# Active_crossover_V12_SMD.net
KiCad netlist of a schematic drawn in EAGLE
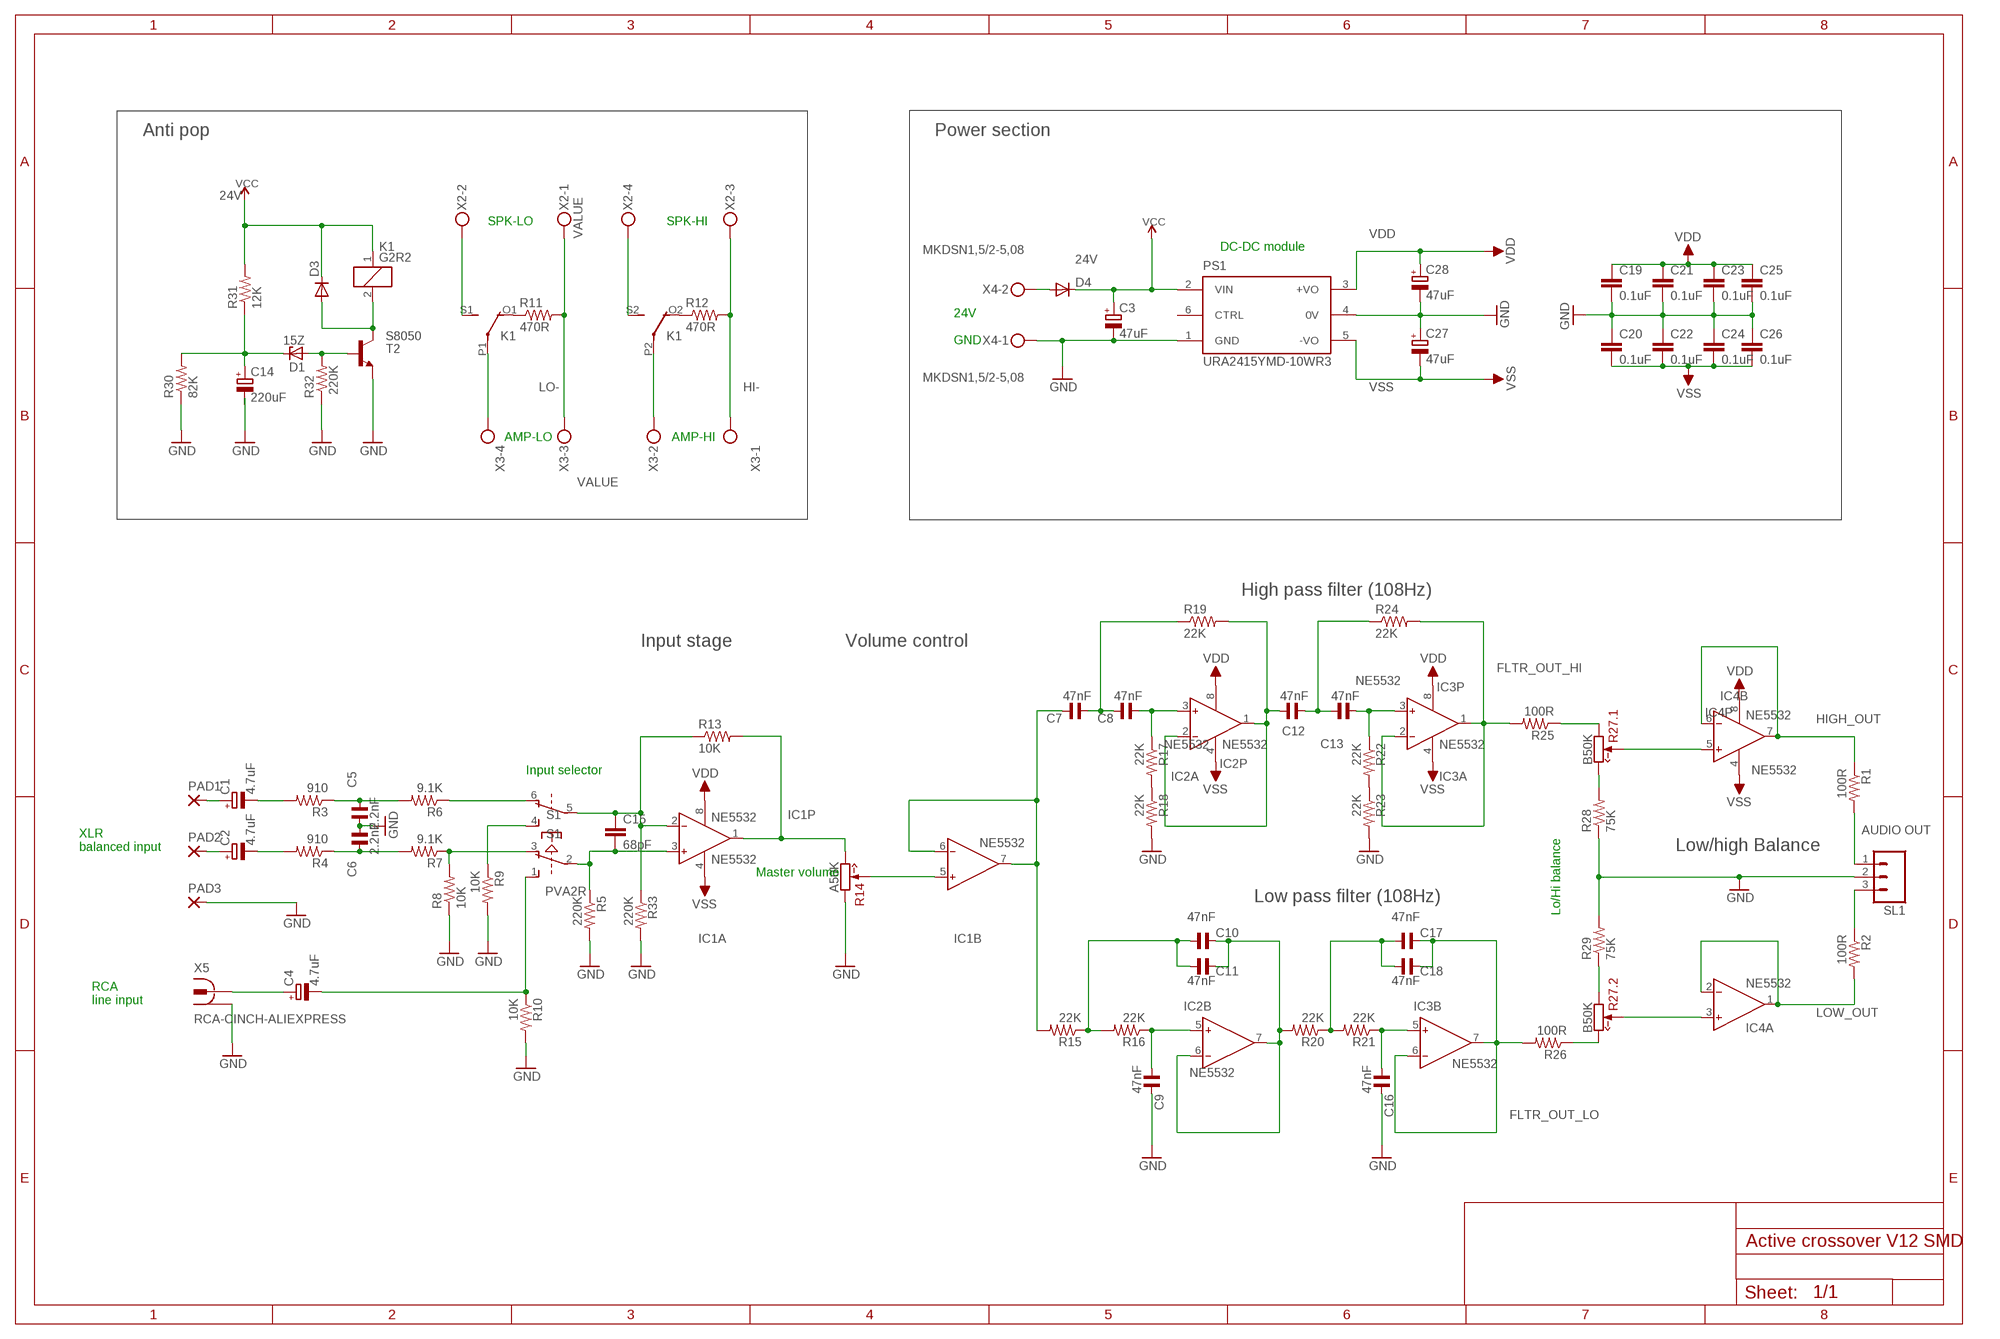
[diagram p0: schematic, sheet 1]

(export (version "E")
  (design (tool "Eeschema 10.0.6"))
  (components
    (comp (ref "C1")
      (value "4.7uF")
      (footprint "eagle-import:E2-5")
      (libsource (lib "eagle-import") (part "rcl_334_CPOL-EUE2-5"))
    )
    (comp (ref "C2")
      (value "4.7uF")
      (footprint "eagle-import:E2-5")
      (libsource (lib "eagle-import") (part "rcl_334_CPOL-EUE2-5"))
    )
    (comp (ref "C3")
      (value "47uF")
      (footprint "eagle-import:E2,5-6")
      (libsource (lib "eagle-import") (part "rcl_334_CPOL-EUE2.5-6"))
    )
    (comp (ref "C4")
      (value "4.7uF")
      (footprint "eagle-import:E2-5")
      (libsource (lib "eagle-import") (part "rcl_334_CPOL-EUE2-5"))
    )
    (comp (ref "C5")
      (value "2.2nF")
      (footprint "eagle-import:C050-025X072")
      (libsource (lib "eagle-import") (part "C_C050-025X072"))
    )
    (comp (ref "C6")
      (value "2.2nF")
      (footprint "eagle-import:C050-025X072")
      (libsource (lib "eagle-import") (part "C_C050-025X072"))
    )
    (comp (ref "C7")
      (value "47nF")
      (footprint "eagle-import:C050-025X072")
      (libsource (lib "eagle-import") (part "C_C050-025X072"))
    )
    (comp (ref "C8")
      (value "47nF")
      (footprint "eagle-import:C050-025X072")
      (libsource (lib "eagle-import") (part "C_C050-025X072"))
    )
    (comp (ref "C9")
      (value "47nF")
      (footprint "eagle-import:C050-025X072")
      (libsource (lib "eagle-import") (part "C_C050-025X072"))
    )
    (comp (ref "C10")
      (value "47nF")
      (footprint "eagle-import:C050-025X072")
      (libsource (lib "eagle-import") (part "C_C050-025X072"))
    )
    (comp (ref "C11")
      (value "47nF")
      (footprint "eagle-import:C050-025X072")
      (libsource (lib "eagle-import") (part "C_C050-025X072"))
    )
    (comp (ref "C12")
      (value "47nF")
      (footprint "eagle-import:C050-025X072")
      (libsource (lib "eagle-import") (part "C_C050-025X072"))
    )
    (comp (ref "C13")
      (value "47nF")
      (footprint "eagle-import:C050-025X072")
      (libsource (lib "eagle-import") (part "C_C050-025X072"))
    )
    (comp (ref "C14")
      (value "220uF")
      (footprint "eagle-import:E3,5-8")
      (libsource (lib "eagle-import") (part "CPOL-EUE3.5-8"))
    )
    (comp (ref "C15")
      (value "68pF")
      (footprint "eagle-import:0603-CAP")
      (libsource (lib "eagle-import") (part "0.1UF-25V-5%(0603)"))
    )
    (comp (ref "C16")
      (value "47nF")
      (footprint "eagle-import:C050-025X072")
      (libsource (lib "eagle-import") (part "C_C050-025X072"))
    )
    (comp (ref "C17")
      (value "47nF")
      (footprint "eagle-import:C050-025X072")
      (libsource (lib "eagle-import") (part "C_C050-025X072"))
    )
    (comp (ref "C18")
      (value "47nF")
      (footprint "eagle-import:C050-025X072")
      (libsource (lib "eagle-import") (part "C_C050-025X072"))
    )
    (comp (ref "C19")
      (value "0.1uF")
      (footprint "eagle-import:0603-CAP")
      (libsource (lib "eagle-import") (part "0.1UF-25V-5%(0603)"))
    )
    (comp (ref "C20")
      (value "0.1uF")
      (footprint "eagle-import:0603-CAP")
      (libsource (lib "eagle-import") (part "0.1UF-25V-5%(0603)"))
    )
    (comp (ref "C21")
      (value "0.1uF")
      (footprint "eagle-import:0603-CAP")
      (libsource (lib "eagle-import") (part "0.1UF-25V-5%(0603)"))
    )
    (comp (ref "C22")
      (value "0.1uF")
      (footprint "eagle-import:0603-CAP")
      (libsource (lib "eagle-import") (part "0.1UF-25V-5%(0603)"))
    )
    (comp (ref "C23")
      (value "0.1uF")
      (footprint "eagle-import:0603-CAP")
      (libsource (lib "eagle-import") (part "0.1UF-25V-5%(0603)"))
    )
    (comp (ref "C24")
      (value "0.1uF")
      (footprint "eagle-import:0603-CAP")
      (libsource (lib "eagle-import") (part "0.1UF-25V-5%(0603)"))
    )
    (comp (ref "C25")
      (value "0.1uF")
      (footprint "eagle-import:0603-CAP")
      (libsource (lib "eagle-import") (part "0.1UF-25V-5%(0603)"))
    )
    (comp (ref "C26")
      (value "0.1uF")
      (footprint "eagle-import:0603-CAP")
      (libsource (lib "eagle-import") (part "0.1UF-25V-5%(0603)"))
    )
    (comp (ref "C27")
      (value "47uF")
      (footprint "eagle-import:E2,5-6")
      (libsource (lib "eagle-import") (part "rcl_334_CPOL-EUE2.5-6"))
    )
    (comp (ref "C28")
      (value "47uF")
      (footprint "eagle-import:E2,5-6")
      (libsource (lib "eagle-import") (part "rcl_334_CPOL-EUE2.5-6"))
    )
    (comp (ref "D1")
      (value "15Z")
      (footprint "eagle-import:ZDIO-7.5")
      (libsource (lib "eagle-import") (part "ZENER-DIODEZD-7.5"))
    )
    (comp (ref "D3")
      (value "DIODESMA-ALT")
      (footprint "eagle-import:SMA-DIODE_ALT")
      (libsource (lib "eagle-import") (part "DIODESMA-ALT"))
    )
    (comp (ref "D4")
      (value "DIODESMB")
      (footprint "eagle-import:SMB-DIODE")
      (libsource (lib "eagle-import") (part "DIODESMB"))
    )
    (comp (ref "IC1")
      (value "NE5532")
      (footprint "eagle-import:DIL08")
      (fields (field (name "MF") "ALTERA CORPORATION") (field (name "MPN") "AD712JNZ"))
      (libsource (lib "eagle-import") (part "AD712N"))
    )
    (comp (ref "IC2")
      (value "NE5532")
      (footprint "eagle-import:DIL08")
      (fields (field (name "MF") "ALTERA CORPORATION") (field (name "MPN") "AD712JNZ"))
      (libsource (lib "eagle-import") (part "AD712N"))
    )
    (comp (ref "IC3")
      (value "NE5532")
      (footprint "eagle-import:DIL08")
      (fields (field (name "MF") "ALTERA CORPORATION") (field (name "MPN") "AD712JNZ"))
      (libsource (lib "eagle-import") (part "AD712N"))
    )
    (comp (ref "IC4")
      (value "NE5532")
      (footprint "eagle-import:DIL08")
      (fields (field (name "MF") "ALTERA CORPORATION") (field (name "MPN") "AD712JNZ"))
      (libsource (lib "eagle-import") (part "AD712N"))
    )
    (comp (ref "K1")
      (value "G2R2")
      (footprint "eagle-import:G2R2")
      (fields (field (name "MANUFACTURER") "OMRON COMPONENTS USA") (field (name "MPN") "G2R-2-DC6"))
      (libsource (lib "eagle-import") (part "G2R2"))
    )
    (comp (ref "PAD1")
      (value "3,17/1,3")
      (footprint "eagle-import:3,17_1,3")
      (libsource (lib "eagle-import") (part "3,17/1,3"))
    )
    (comp (ref "PAD2")
      (value "3,17/1,3")
      (footprint "eagle-import:3,17_1,3")
      (libsource (lib "eagle-import") (part "3,17/1,3"))
    )
    (comp (ref "PAD3")
      (value "3,17/1,3")
      (footprint "eagle-import:3,17_1,3")
      (libsource (lib "eagle-import") (part "3,17/1,3"))
    )
    (comp (ref "PS1")
      (value "URA2415YMD-10WR3")
      (footprint "eagle-import:CONV_URA2405YMD-10WR3")
      (fields (field (name "MANUFACTURER") "Mornsun"))
      (libsource (lib "eagle-import") (part "URA2405YMD-10WR3"))
    )
    (comp (ref "R1")
      (value "100R")
      (footprint "eagle-import:0204_7")
      (libsource (lib "eagle-import") (part "R-US_0204/7"))
    )
    (comp (ref "R2")
      (value "100R")
      (footprint "eagle-import:0204_7")
      (libsource (lib "eagle-import") (part "R-US_0204/7"))
    )
    (comp (ref "R3")
      (value "910")
      (footprint "eagle-import:0204_7")
      (libsource (lib "eagle-import") (part "R-US_0204/7"))
    )
    (comp (ref "R4")
      (value "910")
      (footprint "eagle-import:0204_7")
      (libsource (lib "eagle-import") (part "R-US_0204/7"))
    )
    (comp (ref "R5")
      (value "220K")
      (footprint "eagle-import:0204_7")
      (libsource (lib "eagle-import") (part "R-US_0204/7"))
    )
    (comp (ref "R6")
      (value "9.1K")
      (footprint "eagle-import:0204_7")
      (libsource (lib "eagle-import") (part "R-US_0204/7"))
    )
    (comp (ref "R7")
      (value "9.1K")
      (footprint "eagle-import:0204_7")
      (libsource (lib "eagle-import") (part "R-US_0204/7"))
    )
    (comp (ref "R8")
      (value "10K")
      (footprint "eagle-import:0204_7")
      (libsource (lib "eagle-import") (part "R-US_0204/7"))
    )
    (comp (ref "R9")
      (value "10K")
      (footprint "eagle-import:0204_7")
      (libsource (lib "eagle-import") (part "R-US_0204/7"))
    )
    (comp (ref "R10")
      (value "10K")
      (footprint "eagle-import:0204_7")
      (libsource (lib "eagle-import") (part "R-US_0204/7"))
    )
    (comp (ref "R11")
      (value "470R")
      (footprint "eagle-import:0204_7")
      (libsource (lib "eagle-import") (part "R-US_0204/7"))
    )
    (comp (ref "R12")
      (value "470R")
      (footprint "eagle-import:0204_7")
      (libsource (lib "eagle-import") (part "R-US_0204/7"))
    )
    (comp (ref "R13")
      (value "10K")
      (footprint "eagle-import:0204_7")
      (libsource (lib "eagle-import") (part "R-US_0204/7"))
    )
    (comp (ref "R14")
      (value "A50K")
      (footprint "eagle-import:RV09-SINGLE")
      (libsource (lib "eagle-import") (part "?A10K(9MM)"))
    )
    (comp (ref "R15")
      (value "22K")
      (footprint "eagle-import:0204_7")
      (libsource (lib "eagle-import") (part "R-US_0204/7"))
    )
    (comp (ref "R16")
      (value "22K")
      (footprint "eagle-import:0204_7")
      (libsource (lib "eagle-import") (part "R-US_0204/7"))
    )
    (comp (ref "R17")
      (value "22K")
      (footprint "eagle-import:0204_7")
      (libsource (lib "eagle-import") (part "R-US_0204/7"))
    )
    (comp (ref "R18")
      (value "22K")
      (footprint "eagle-import:0204_7")
      (libsource (lib "eagle-import") (part "R-US_0204/7"))
    )
    (comp (ref "R19")
      (value "22K")
      (footprint "eagle-import:0204_7")
      (libsource (lib "eagle-import") (part "R-US_0204/7"))
    )
    (comp (ref "R20")
      (value "22K")
      (footprint "eagle-import:0204_7")
      (libsource (lib "eagle-import") (part "R-US_0204/7"))
    )
    (comp (ref "R21")
      (value "22K")
      (footprint "eagle-import:0204_7")
      (libsource (lib "eagle-import") (part "R-US_0204/7"))
    )
    (comp (ref "R22")
      (value "22K")
      (footprint "eagle-import:0204_7")
      (libsource (lib "eagle-import") (part "R-US_0204/7"))
    )
    (comp (ref "R23")
      (value "22K")
      (footprint "eagle-import:0204_7")
      (libsource (lib "eagle-import") (part "R-US_0204/7"))
    )
    (comp (ref "R24")
      (value "22K")
      (footprint "eagle-import:0204_7")
      (libsource (lib "eagle-import") (part "R-US_0204/7"))
    )
    (comp (ref "R25")
      (value "100R")
      (footprint "eagle-import:0204_7")
      (libsource (lib "eagle-import") (part "R-US_0204/7"))
    )
    (comp (ref "R26")
      (value "100R")
      (footprint "eagle-import:0204_7")
      (libsource (lib "eagle-import") (part "R-US_0204/7"))
    )
    (comp (ref "R27")
      (value "B50K")
      (footprint "eagle-import:RK14-DUAL")
      (libsource (lib "eagle-import") (part "7PIN"))
    )
    (comp (ref "R28")
      (value "75K")
      (footprint "eagle-import:0204_7")
      (libsource (lib "eagle-import") (part "R-US_0204/7"))
    )
    (comp (ref "R29")
      (value "75K")
      (footprint "eagle-import:0204_7")
      (libsource (lib "eagle-import") (part "R-US_0204/7"))
    )
    (comp (ref "R30")
      (value "82K")
      (footprint "eagle-import:M0805")
      (libsource (lib "eagle-import") (part "R-US_M0805"))
    )
    (comp (ref "R31")
      (value "12K")
      (footprint "eagle-import:M0805")
      (libsource (lib "eagle-import") (part "R-US_M0805"))
    )
    (comp (ref "R32")
      (value "220K")
      (footprint "eagle-import:M0805")
      (libsource (lib "eagle-import") (part "R-US_M0805"))
    )
    (comp (ref "R33")
      (value "220K")
      (footprint "eagle-import:0204_7")
      (libsource (lib "eagle-import") (part "R-US_0204/7"))
    )
    (comp (ref "S1")
      (value "PVA2R")
      (footprint "eagle-import:PVA2R")
      (libsource (lib "eagle-import") (part "PVA2R"))
    )
    (comp (ref "SL1")
      (value "AUDIO OUT")
      (footprint "eagle-import:03P")
      (libsource (lib "eagle-import") (part "M03"))
    )
    (comp (ref "T2")
      (value "S8050")
      (footprint "eagle-import:SOT23")
      (libsource (lib "eagle-import") (part "BC846"))
    )
    (comp (ref "X2")
      (value "MKDSN1,5/4-5,08")
      (footprint "eagle-import:MKDSN1,5_4-5,08")
      (libsource (lib "eagle-import") (part "MKDSN1,5/4-5,08"))
    )
    (comp (ref "X3")
      (value "MKDSN1,5/4-5,08")
      (footprint "eagle-import:MKDSN1,5_4-5,08")
      (libsource (lib "eagle-import") (part "MKDSN1,5/4-5,08"))
    )
    (comp (ref "X4")
      (value "MKDSN1,5/2-5,08")
      (footprint "eagle-import:MKDSN1,5_2-5,08")
      (libsource (lib "eagle-import") (part "MKDSN1,5/2-5,08"))
    )
    (comp (ref "X5")
      (value "RCA-CINCH-ALIEXPRESS")
      (footprint "eagle-import:RCA-CINCH-ALIEXPRESS")
      (libsource (lib "eagle-import") (part "RCA-CINCH-ALIEXPRESS"))
    )
  )
  (nets
    (net (code "1") (name "/FLTR_OUT_HI") (class "Default")
      (node (ref "IC3") (pin "1") (pinfunction "OUT_1") (pintype "output"))
      (node (ref "IC3") (pin "2") (pinfunction "IN-_2") (pintype "input"))
      (node (ref "R24") (pin "2") (pinfunction "2_2") (pintype "passive"))
      (node (ref "R25") (pin "2") (pinfunction "2_2") (pintype "passive"))
    )
    (net (code "2") (name "/FLTR_OUT_LO") (class "Default")
      (node (ref "C17") (pin "2") (pinfunction "2_2") (pintype "passive"))
      (node (ref "C18") (pin "2") (pinfunction "2_2") (pintype "passive"))
      (node (ref "IC3") (pin "6") (pinfunction "IN-_6") (pintype "input"))
      (node (ref "IC3") (pin "7") (pinfunction "OUT_7") (pintype "output"))
      (node (ref "R26") (pin "2") (pinfunction "2_2") (pintype "passive"))
    )
    (net (code "3") (name "/HI-") (class "Default")
      (node (ref "R12") (pin "2") (pinfunction "2_2") (pintype "passive"))
      (node (ref "X2") (pin "3") (pinfunction "KL_3") (pintype "passive"))
      (node (ref "X3") (pin "1") (pinfunction "KL_1") (pintype "passive"))
    )
    (net (code "4") (name "/HIGH_OUT") (class "Default")
      (node (ref "IC4") (pin "6") (pinfunction "IN-_6") (pintype "input"))
      (node (ref "IC4") (pin "7") (pinfunction "OUT_7") (pintype "output"))
      (node (ref "R1") (pin "1") (pinfunction "1_1") (pintype "passive"))
    )
    (net (code "5") (name "/LO-") (class "Default")
      (node (ref "R11") (pin "2") (pinfunction "2_2") (pintype "passive"))
      (node (ref "X2") (pin "1") (pinfunction "KL_1") (pintype "passive"))
      (node (ref "X3") (pin "3") (pinfunction "KL_3") (pintype "passive"))
    )
    (net (code "6") (name "/LOW_OUT") (class "Default")
      (node (ref "IC4") (pin "1") (pinfunction "OUT_1") (pintype "output"))
      (node (ref "IC4") (pin "2") (pinfunction "IN-_2") (pintype "input"))
      (node (ref "R2") (pin "2") (pinfunction "2_2") (pintype "passive"))
    )
    (net (code "7") (name "GND") (class "Default")
      (node (ref "C14") (pin "-") (pinfunction "-_-") (pintype "passive"))
      (node (ref "C16") (pin "2") (pinfunction "2_2") (pintype "passive"))
      (node (ref "C19") (pin "2") (pinfunction "2_2") (pintype "passive"))
      (node (ref "C20") (pin "1") (pinfunction "1_1") (pintype "passive"))
      (node (ref "C21") (pin "2") (pinfunction "2_2") (pintype "passive"))
      (node (ref "C22") (pin "1") (pinfunction "1_1") (pintype "passive"))
      (node (ref "C23") (pin "2") (pinfunction "2_2") (pintype "passive"))
      (node (ref "C24") (pin "1") (pinfunction "1_1") (pintype "passive"))
      (node (ref "C25") (pin "2") (pinfunction "2_2") (pintype "passive"))
      (node (ref "C26") (pin "1") (pinfunction "1_1") (pintype "passive"))
      (node (ref "C27") (pin "+") (pinfunction "+_+") (pintype "passive"))
      (node (ref "C28") (pin "-") (pinfunction "-_-") (pintype "passive"))
      (node (ref "C3") (pin "-") (pinfunction "-_-") (pintype "passive"))
      (node (ref "C5") (pin "1") (pinfunction "1_1") (pintype "passive"))
      (node (ref "C6") (pin "2") (pinfunction "2_2") (pintype "passive"))
      (node (ref "C9") (pin "2") (pinfunction "2_2") (pintype "passive"))
      (node (ref "PAD3") (pin "1") (pinfunction "P_1") (pintype "passive"))
      (node (ref "PS1") (pin "1") (pinfunction "GND_1") (pintype "power_in"))
      (node (ref "PS1") (pin "4") (pinfunction "0V_4") (pintype "passive"))
      (node (ref "R10") (pin "2") (pinfunction "2_2") (pintype "passive"))
      (node (ref "R14") (pin "1") (pinfunction "CCW_1") (pintype "passive"))
      (node (ref "R18") (pin "2") (pinfunction "2_2") (pintype "passive"))
      (node (ref "R23") (pin "2") (pinfunction "2_2") (pintype "passive"))
      (node (ref "R28") (pin "1") (pinfunction "1_1") (pintype "passive"))
      (node (ref "R29") (pin "2") (pinfunction "2_2") (pintype "passive"))
      (node (ref "R30") (pin "1") (pinfunction "1_1") (pintype "passive"))
      (node (ref "R32") (pin "1") (pinfunction "1_1") (pintype "passive"))
      (node (ref "R33") (pin "2") (pinfunction "2_2") (pintype "passive"))
      (node (ref "R5") (pin "2") (pinfunction "2_2") (pintype "passive"))
      (node (ref "R8") (pin "1") (pinfunction "1_1") (pintype "passive"))
      (node (ref "R9") (pin "2") (pinfunction "2_2") (pintype "passive"))
      (node (ref "SL1") (pin "2") (pinfunction "2_2") (pintype "passive"))
      (node (ref "T2") (pin "2") (pinfunction "E_2") (pintype "passive"))
      (node (ref "X4") (pin "1") (pinfunction "KL_1") (pintype "passive"))
      (node (ref "X5") (pin "P$1") (pinfunction "1_P$1") (pintype "passive"))
      (node (ref "X5") (pin "P$3") (pinfunction "1_P$3") (pintype "passive"))
    )
    (net (code "8") (name "Net-(C1-Pad-)") (class "Default")
      (node (ref "C1") (pin "-") (pinfunction "-_-") (pintype "passive"))
      (node (ref "R3") (pin "2") (pinfunction "2_2") (pintype "passive"))
    )
    (net (code "9") (name "Net-(C2-Pad-)") (class "Default")
      (node (ref "C2") (pin "-") (pinfunction "-_-") (pintype "passive"))
      (node (ref "R4") (pin "2") (pinfunction "2_2") (pintype "passive"))
    )
    (net (code "10") (name "Net-(C5-Pad2)") (class "Default")
      (node (ref "C5") (pin "2") (pinfunction "2_2") (pintype "passive"))
      (node (ref "R3") (pin "1") (pinfunction "1_1") (pintype "passive"))
      (node (ref "R6") (pin "2") (pinfunction "2_2") (pintype "passive"))
    )
    (net (code "11") (name "Net-(C6-Pad1)") (class "Default")
      (node (ref "C6") (pin "1") (pinfunction "1_1") (pintype "passive"))
      (node (ref "R4") (pin "1") (pinfunction "1_1") (pintype "passive"))
      (node (ref "R7") (pin "2") (pinfunction "2_2") (pintype "passive"))
    )
    (net (code "12") (name "Net-(C7-Pad1)") (class "Default")
      (node (ref "C7") (pin "1") (pinfunction "1_1") (pintype "passive"))
      (node (ref "C8") (pin "2") (pinfunction "2_2") (pintype "passive"))
      (node (ref "R19") (pin "1") (pinfunction "1_1") (pintype "passive"))
    )
    (net (code "13") (name "Net-(C10-Pad1)") (class "Default")
      (node (ref "C10") (pin "1") (pinfunction "1_1") (pintype "passive"))
      (node (ref "C11") (pin "1") (pinfunction "1_1") (pintype "passive"))
      (node (ref "R15") (pin "1") (pinfunction "1_1") (pintype "passive"))
      (node (ref "R16") (pin "2") (pinfunction "2_2") (pintype "passive"))
    )
    (net (code "14") (name "Net-(C12-Pad1)") (class "Default")
      (node (ref "C12") (pin "1") (pinfunction "1_1") (pintype "passive"))
      (node (ref "C13") (pin "2") (pinfunction "2_2") (pintype "passive"))
      (node (ref "R24") (pin "1") (pinfunction "1_1") (pintype "passive"))
    )
    (net (code "15") (name "Net-(C14-Pad+)") (class "Default")
      (node (ref "C14") (pin "+") (pinfunction "+_+") (pintype "passive"))
      (node (ref "D1") (pin "C") (pinfunction "C_C") (pintype "passive"))
      (node (ref "R30") (pin "2") (pinfunction "2_2") (pintype "passive"))
      (node (ref "R31") (pin "1") (pinfunction "1_1") (pintype "passive"))
    )
    (net (code "16") (name "Net-(C17-Pad1)") (class "Default")
      (node (ref "C17") (pin "1") (pinfunction "1_1") (pintype "passive"))
      (node (ref "C18") (pin "1") (pinfunction "1_1") (pintype "passive"))
      (node (ref "R20") (pin "1") (pinfunction "1_1") (pintype "passive"))
      (node (ref "R21") (pin "2") (pinfunction "2_2") (pintype "passive"))
    )
    (net (code "17") (name "Net-(IC1A-IN+)") (class "Default")
      (node (ref "C15") (pin "2") (pinfunction "2_2") (pintype "passive"))
      (node (ref "IC1") (pin "3") (pinfunction "IN+_3") (pintype "input"))
      (node (ref "R5") (pin "1") (pinfunction "1_1") (pintype "passive"))
      (node (ref "S1") (pin "2") (pinfunction "P_2") (pintype "passive"))
    )
    (net (code "18") (name "Net-(IC1A-IN-)") (class "Default")
      (node (ref "C15") (pin "1") (pinfunction "1_1") (pintype "passive"))
      (node (ref "IC1") (pin "2") (pinfunction "IN-_2") (pintype "input"))
      (node (ref "R13") (pin "1") (pinfunction "1_1") (pintype "passive"))
      (node (ref "R33") (pin "1") (pinfunction "1_1") (pintype "passive"))
      (node (ref "S1") (pin "5") (pinfunction "P_5") (pintype "passive"))
    )
    (net (code "19") (name "Net-(IC1A-OUT)") (class "Default")
      (node (ref "IC1") (pin "1") (pinfunction "OUT_1") (pintype "output"))
      (node (ref "R13") (pin "2") (pinfunction "2_2") (pintype "passive"))
      (node (ref "R14") (pin "3") (pinfunction "CW_3") (pintype "passive"))
    )
    (net (code "20") (name "Net-(IC1B-IN+)") (class "Default")
      (node (ref "IC1") (pin "5") (pinfunction "IN+_5") (pintype "input"))
      (node (ref "R14") (pin "2") (pinfunction "W_2") (pintype "passive"))
    )
    (net (code "21") (name "Net-(IC1B-IN-)") (class "Default")
      (node (ref "C7") (pin "2") (pinfunction "2_2") (pintype "passive"))
      (node (ref "IC1") (pin "6") (pinfunction "IN-_6") (pintype "input"))
      (node (ref "IC1") (pin "7") (pinfunction "OUT_7") (pintype "output"))
      (node (ref "R15") (pin "2") (pinfunction "2_2") (pintype "passive"))
    )
    (net (code "22") (name "Net-(IC2A-IN+)") (class "Default")
      (node (ref "C8") (pin "1") (pinfunction "1_1") (pintype "passive"))
      (node (ref "IC2") (pin "3") (pinfunction "IN+_3") (pintype "input"))
      (node (ref "R17") (pin "1") (pinfunction "1_1") (pintype "passive"))
    )
    (net (code "23") (name "Net-(IC2A-IN-)") (class "Default")
      (node (ref "C12") (pin "2") (pinfunction "2_2") (pintype "passive"))
      (node (ref "IC2") (pin "1") (pinfunction "OUT_1") (pintype "output"))
      (node (ref "IC2") (pin "2") (pinfunction "IN-_2") (pintype "input"))
      (node (ref "R19") (pin "2") (pinfunction "2_2") (pintype "passive"))
    )
    (net (code "24") (name "Net-(IC2B-IN+)") (class "Default")
      (node (ref "C9") (pin "1") (pinfunction "1_1") (pintype "passive"))
      (node (ref "IC2") (pin "5") (pinfunction "IN+_5") (pintype "input"))
      (node (ref "R16") (pin "1") (pinfunction "1_1") (pintype "passive"))
    )
    (net (code "25") (name "Net-(IC2B-IN-)") (class "Default")
      (node (ref "C10") (pin "2") (pinfunction "2_2") (pintype "passive"))
      (node (ref "C11") (pin "2") (pinfunction "2_2") (pintype "passive"))
      (node (ref "IC2") (pin "6") (pinfunction "IN-_6") (pintype "input"))
      (node (ref "IC2") (pin "7") (pinfunction "OUT_7") (pintype "output"))
      (node (ref "R20") (pin "2") (pinfunction "2_2") (pintype "passive"))
    )
    (net (code "26") (name "Net-(IC3A-IN+)") (class "Default")
      (node (ref "C13") (pin "1") (pinfunction "1_1") (pintype "passive"))
      (node (ref "IC3") (pin "3") (pinfunction "IN+_3") (pintype "input"))
      (node (ref "R22") (pin "1") (pinfunction "1_1") (pintype "passive"))
    )
    (net (code "27") (name "Net-(IC3B-IN+)") (class "Default")
      (node (ref "C16") (pin "1") (pinfunction "1_1") (pintype "passive"))
      (node (ref "IC3") (pin "5") (pinfunction "IN+_5") (pintype "input"))
      (node (ref "R21") (pin "1") (pinfunction "1_1") (pintype "passive"))
    )
    (net (code "28") (name "Net-(IC4A-IN+)") (class "Default")
      (node (ref "IC4") (pin "3") (pinfunction "IN+_3") (pintype "input"))
      (node (ref "R27") (pin "2") (pinfunction "W_2") (pintype "passive"))
    )
    (net (code "29") (name "Net-(IC4B-IN+)") (class "Default")
      (node (ref "IC4") (pin "5") (pinfunction "IN+_5") (pintype "input"))
      (node (ref "R27") (pin "2'") (pinfunction "W_2'") (pintype "passive"))
    )
    (net (code "30") (name "Net-(K1B-O)") (class "Default")
      (node (ref "K1") (pin "O1") (pinfunction "O_O1") (pintype "passive"))
      (node (ref "R11") (pin "1") (pinfunction "1_1") (pintype "passive"))
    )
    (net (code "31") (name "Net-(K1B-P)") (class "Default")
      (node (ref "K1") (pin "P1") (pinfunction "P_P1") (pintype "passive"))
      (node (ref "X3") (pin "4") (pinfunction "KL_4") (pintype "passive"))
    )
    (net (code "32") (name "Net-(K1B-S)") (class "Default")
      (node (ref "K1") (pin "S1") (pinfunction "S_S1") (pintype "passive"))
      (node (ref "X2") (pin "2") (pinfunction "KL_2") (pintype "passive"))
    )
    (net (code "33") (name "Net-(K1C-O)") (class "Default")
      (node (ref "K1") (pin "O2") (pinfunction "O_O2") (pintype "passive"))
      (node (ref "R12") (pin "1") (pinfunction "1_1") (pintype "passive"))
    )
    (net (code "34") (name "Net-(K1C-P)") (class "Default")
      (node (ref "K1") (pin "P2") (pinfunction "P_P2") (pintype "passive"))
      (node (ref "X3") (pin "2") (pinfunction "KL_2") (pintype "passive"))
    )
    (net (code "35") (name "Net-(K1C-S)") (class "Default")
      (node (ref "K1") (pin "S2") (pinfunction "S_S2") (pintype "passive"))
      (node (ref "X2") (pin "4") (pinfunction "KL_4") (pintype "passive"))
    )
    (net (code "36") (name "Net-(PAD1-P)") (class "Default")
      (node (ref "C1") (pin "+") (pinfunction "+_+") (pintype "passive"))
      (node (ref "PAD1") (pin "1") (pinfunction "P_1") (pintype "passive"))
    )
    (net (code "37") (name "Net-(PAD2-P)") (class "Default")
      (node (ref "C2") (pin "+") (pinfunction "+_+") (pintype "passive"))
      (node (ref "PAD2") (pin "1") (pinfunction "P_1") (pintype "passive"))
    )
    (net (code "38") (name "Net-(R1-Pad2)") (class "Default")
      (node (ref "R1") (pin "2") (pinfunction "2_2") (pintype "passive"))
      (node (ref "SL1") (pin "1") (pinfunction "1_1") (pintype "passive"))
    )
    (net (code "39") (name "Net-(R2-Pad1)") (class "Default")
      (node (ref "R2") (pin "1") (pinfunction "1_1") (pintype "passive"))
      (node (ref "SL1") (pin "3") (pinfunction "3_3") (pintype "passive"))
    )
    (net (code "40") (name "Net-(R17-Pad2)") (class "Default")
      (node (ref "R17") (pin "2") (pinfunction "2_2") (pintype "passive"))
      (node (ref "R18") (pin "1") (pinfunction "1_1") (pintype "passive"))
    )
    (net (code "41") (name "Net-(R22-Pad2)") (class "Default")
      (node (ref "R22") (pin "2") (pinfunction "2_2") (pintype "passive"))
      (node (ref "R23") (pin "1") (pinfunction "1_1") (pintype "passive"))
    )
    (net (code "42") (name "Net-(R27A-CCW)") (class "Default")
      (node (ref "R25") (pin "1") (pinfunction "1_1") (pintype "passive"))
      (node (ref "R27") (pin "3'") (pinfunction "CCW_3'") (pintype "passive"))
    )
    (net (code "43") (name "Net-(R27A-CW)") (class "Default")
      (node (ref "R27") (pin "1'") (pinfunction "CW_1'") (pintype "passive"))
      (node (ref "R28") (pin "2") (pinfunction "2_2") (pintype "passive"))
    )
    (net (code "44") (name "Net-(R27B-CCW)") (class "Default")
      (node (ref "R27") (pin "3") (pinfunction "CCW_3") (pintype "passive"))
      (node (ref "R29") (pin "1") (pinfunction "1_1") (pintype "passive"))
    )
    (net (code "45") (name "Net-(R27B-CW)") (class "Default")
      (node (ref "R26") (pin "1") (pinfunction "1_1") (pintype "passive"))
      (node (ref "R27") (pin "1") (pinfunction "CW_1") (pintype "passive"))
    )
    (net (code "46") (name "Net-(S1A-O)") (class "Default")
      (node (ref "R7") (pin "1") (pinfunction "1_1") (pintype "passive"))
      (node (ref "R8") (pin "2") (pinfunction "2_2") (pintype "passive"))
      (node (ref "S1") (pin "3") (pinfunction "O_3") (pintype "passive"))
    )
    (net (code "47") (name "Net-(S1A-S)") (class "Default")
      (node (ref "C4") (pin "-") (pinfunction "-_-") (pintype "passive"))
      (node (ref "R10") (pin "1") (pinfunction "1_1") (pintype "passive"))
      (node (ref "S1") (pin "1") (pinfunction "S_1") (pintype "passive"))
    )
    (net (code "48") (name "Net-(S1B-O)") (class "Default")
      (node (ref "R6") (pin "1") (pinfunction "1_1") (pintype "passive"))
      (node (ref "S1") (pin "6") (pinfunction "O_6") (pintype "passive"))
    )
    (net (code "49") (name "Net-(S1B-S)") (class "Default")
      (node (ref "R9") (pin "1") (pinfunction "1_1") (pintype "passive"))
      (node (ref "S1") (pin "4") (pinfunction "S_4") (pintype "passive"))
    )
    (net (code "50") (name "Net-(T2-B)") (class "Default")
      (node (ref "D1") (pin "A") (pinfunction "A_A") (pintype "passive"))
      (node (ref "R32") (pin "2") (pinfunction "2_2") (pintype "passive"))
      (node (ref "T2") (pin "1") (pinfunction "B_1") (pintype "passive"))
    )
    (net (code "51") (name "Net-(T2-C)") (class "Default")
      (node (ref "D3") (pin "A") (pinfunction "A_A") (pintype "passive"))
      (node (ref "K1") (pin "2") (pinfunction "2_2") (pintype "passive"))
      (node (ref "T2") (pin "3") (pinfunction "C_3") (pintype "passive"))
    )
    (net (code "52") (name "Net-(X4B-KL)") (class "Default")
      (node (ref "D4") (pin "A") (pinfunction "A_A") (pintype "passive"))
      (node (ref "X4") (pin "2") (pinfunction "KL_2") (pintype "passive"))
    )
    (net (code "53") (name "Net-(X5-2)") (class "Default")
      (node (ref "C4") (pin "+") (pinfunction "+_+") (pintype "passive"))
      (node (ref "X5") (pin "P$2") (pinfunction "2_P$2") (pintype "passive"))
    )
    (net (code "54") (name "VCC") (class "Default")
      (node (ref "C3") (pin "+") (pinfunction "+_+") (pintype "passive"))
      (node (ref "D3") (pin "C") (pinfunction "C_C") (pintype "passive"))
      (node (ref "D4") (pin "C") (pinfunction "C_C") (pintype "passive"))
      (node (ref "K1") (pin "1") (pinfunction "1_1") (pintype "passive"))
      (node (ref "PS1") (pin "2") (pinfunction "VIN_2") (pintype "input"))
      (node (ref "R31") (pin "2") (pinfunction "2_2") (pintype "passive"))
    )
    (net (code "55") (name "VDD") (class "Default")
      (node (ref "C19") (pin "1") (pinfunction "1_1") (pintype "passive"))
      (node (ref "C21") (pin "1") (pinfunction "1_1") (pintype "passive"))
      (node (ref "C23") (pin "1") (pinfunction "1_1") (pintype "passive"))
      (node (ref "C25") (pin "1") (pinfunction "1_1") (pintype "passive"))
      (node (ref "C28") (pin "+") (pinfunction "+_+") (pintype "passive"))
      (node (ref "IC1") (pin "8") (pinfunction "V+_8") (pintype "power_in"))
      (node (ref "IC2") (pin "8") (pinfunction "V+_8") (pintype "power_in"))
      (node (ref "IC3") (pin "8") (pinfunction "V+_8") (pintype "power_in"))
      (node (ref "IC4") (pin "8") (pinfunction "V+_8") (pintype "power_in"))
      (node (ref "PS1") (pin "3") (pinfunction "+VO_3") (pintype "output"))
    )
    (net (code "56") (name "VSS") (class "Default")
      (node (ref "C20") (pin "2") (pinfunction "2_2") (pintype "passive"))
      (node (ref "C22") (pin "2") (pinfunction "2_2") (pintype "passive"))
      (node (ref "C24") (pin "2") (pinfunction "2_2") (pintype "passive"))
      (node (ref "C26") (pin "2") (pinfunction "2_2") (pintype "passive"))
      (node (ref "C27") (pin "-") (pinfunction "-_-") (pintype "passive"))
      (node (ref "IC1") (pin "4") (pinfunction "V-_4") (pintype "power_in"))
      (node (ref "IC2") (pin "4") (pinfunction "V-_4") (pintype "power_in"))
      (node (ref "IC3") (pin "4") (pinfunction "V-_4") (pintype "power_in"))
      (node (ref "IC4") (pin "4") (pinfunction "V-_4") (pintype "power_in"))
      (node (ref "PS1") (pin "5") (pinfunction "-VO_5") (pintype "output"))
    )
    (net (code "57") (name "unconnected-(PS1-CTRL-Pad6)") (class "Default")
      (node (ref "PS1") (pin "6") (pinfunction "CTRL_6") (pintype "input"))
    )
  )
)
